# MIC2.net
KiCad netlist of a schematic drawn in Altium Designer
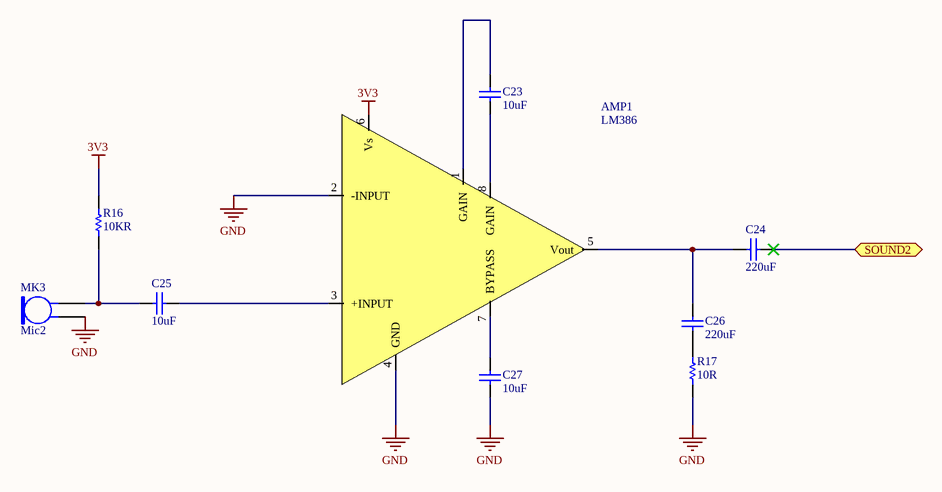
[diagram p0: MIC2.SchDoc]

(export (version "E")
  (design (tool "Eeschema 10.0.6"))
  (components
    (comp (ref "AMP1") (value "LM386") (footprint "Ampli") (libsource (lib "SCHLIB_Autobot") (part "LM386")))
    (comp (ref "C23")
      (value "10uF")
      (footprint "CAPC1608N")
      (description "Capacitor")
      (fields (field (name "PUBLISHER") "Altium Limited"))
      (libsource (lib "Miscellaneous Devices") (part "Cap"))
    )
    (comp (ref "C24")
      (value "220uF")
      (footprint "CAPC1608N")
      (description "Capacitor")
      (fields (field (name "PUBLISHER") "Altium Limited"))
      (libsource (lib "Miscellaneous Devices") (part "Cap"))
    )
    (comp (ref "C25")
      (value "10uF")
      (footprint "CAPC1608N")
      (description "Capacitor")
      (fields (field (name "PUBLISHER") "Altium Limited"))
      (libsource (lib "Miscellaneous Devices") (part "Cap"))
    )
    (comp (ref "C26")
      (value "220uF")
      (footprint "CAPC1608N")
      (description "Capacitor")
      (fields (field (name "PUBLISHER") "Altium Limited"))
      (libsource (lib "Miscellaneous Devices") (part "Cap"))
    )
    (comp (ref "C27")
      (value "10uF")
      (footprint "CAPC1608N")
      (description "Capacitor")
      (fields (field (name "PUBLISHER") "Altium Limited"))
      (libsource (lib "Miscellaneous Devices") (part "Cap"))
    )
    (comp (ref "MK3")
      (value "Mic2")
      (footprint "PIN2")
      (description "Microphone")
      (fields (field (name "PUBLISHER") "Altium Limited"))
      (libsource (lib "Miscellaneous Devices") (part "Mic2"))
    )
    (comp (ref "R16")
      (value "10KR")
      (footprint "RESC1608N")
      (description "Resistor")
      (fields (field (name "PUBLISHER") "Altium Limited"))
      (libsource (lib "Miscellaneous Devices") (part "Res1"))
    )
    (comp (ref "R17")
      (value "10R")
      (footprint "RESC1608N")
      (description "Resistor")
      (fields (field (name "PUBLISHER") "Altium Limited"))
      (libsource (lib "Miscellaneous Devices") (part "Res1"))
    )
  )
  (nets
    (net (code "1") (name "/SOUND2") (class "Default")
      (node (ref "C24") (pin "1") (pinfunction "1_1") (pintype "passive+no_connect"))
    )
    (net (code "2") (name "3V3") (class "Default")
      (node (ref "AMP1") (pin "6") (pinfunction "Vs_6") (pintype "passive"))
      (node (ref "R16") (pin "1") (pinfunction "1_1") (pintype "passive"))
    )
    (net (code "3") (name "GND") (class "Default")
      (node (ref "AMP1") (pin "2") (pinfunction "-INPUT_2") (pintype "passive"))
      (node (ref "AMP1") (pin "4") (pinfunction "GND_4") (pintype "passive"))
      (node (ref "C27") (pin "2") (pinfunction "2_2") (pintype "passive"))
      (node (ref "MK3") (pin "1") (pinfunction "1_1") (pintype "passive"))
      (node (ref "R17") (pin "2") (pinfunction "2_2") (pintype "passive"))
    )
    (net (code "4") (name "Net-(AMP1-+INPUT)") (class "Default")
      (node (ref "AMP1") (pin "3") (pinfunction "+INPUT_3") (pintype "passive"))
      (node (ref "C25") (pin "1") (pinfunction "1_1") (pintype "passive"))
    )
    (net (code "5") (name "Net-(AMP1-BYPASS)") (class "Default")
      (node (ref "AMP1") (pin "7") (pinfunction "BYPASS_7") (pintype "passive"))
      (node (ref "C27") (pin "1") (pinfunction "1_1") (pintype "passive"))
    )
    (net (code "6") (name "Net-(AMP1-GAIN-Pad1)") (class "Default")
      (node (ref "AMP1") (pin "1") (pinfunction "GAIN_1") (pintype "passive"))
      (node (ref "C23") (pin "1") (pinfunction "1_1") (pintype "passive"))
    )
    (net (code "7") (name "Net-(AMP1-GAIN-Pad8)") (class "Default")
      (node (ref "AMP1") (pin "8") (pinfunction "GAIN_8") (pintype "passive"))
      (node (ref "C23") (pin "2") (pinfunction "2_2") (pintype "passive"))
    )
    (net (code "8") (name "Net-(AMP1-Vout)") (class "Default")
      (node (ref "AMP1") (pin "5") (pinfunction "Vout_5") (pintype "passive"))
      (node (ref "C24") (pin "2") (pinfunction "2_2") (pintype "passive"))
      (node (ref "C26") (pin "1") (pinfunction "1_1") (pintype "passive"))
    )
    (net (code "9") (name "Net-(C25-Pad2)") (class "Default")
      (node (ref "C25") (pin "2") (pinfunction "2_2") (pintype "passive"))
      (node (ref "MK3") (pin "2") (pinfunction "2_2") (pintype "passive"))
      (node (ref "R16") (pin "2") (pinfunction "2_2") (pintype "passive"))
    )
    (net (code "10") (name "Net-(C26-Pad2)") (class "Default")
      (node (ref "C26") (pin "2") (pinfunction "2_2") (pintype "passive"))
      (node (ref "R17") (pin "1") (pinfunction "1_1") (pintype "passive"))
    )
  )
)
